# FIT_FPGA_POWER.net
KiCad netlist of a schematic drawn in Altium Designer
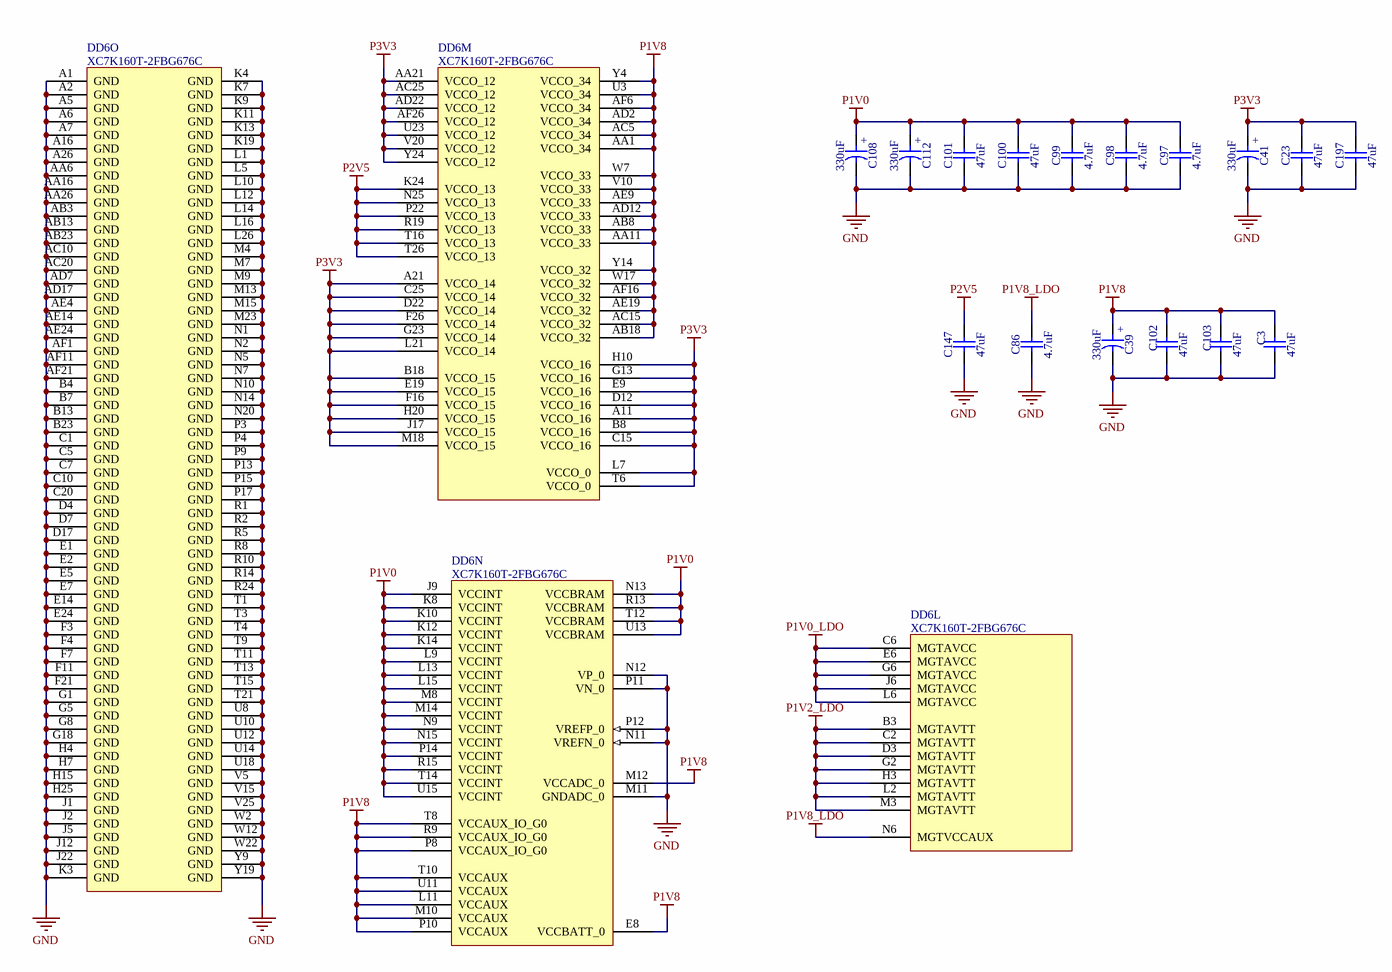
[diagram p0: FIT_FPGA_POWER.SchDoc]

(export (version "E")
  (design (tool "Eeschema 10.0.6"))
  (components
    (comp (ref "C3")
      (value "47uF")
      (footprint "CAPC3225X270N")
      (description "Non-polarised capacitor")
      (fields
        (field (name "PART NUMBER") "CC1210_47UF_16V_20%_X5R")
        (field (name "VOLTAGE") "16V")
        (field (name "AUTHOR") "CERN DEM MR")
      )
      (libsource (lib "Capacitors") (part "Capacitor - non polarized"))
    )
    (comp (ref "C23")
      (value "47uF")
      (footprint "CAPC3225X270N")
      (description "Non-polarised capacitor")
      (fields
        (field (name "PART NUMBER") "CC1210_47UF_16V_20%_X5R")
        (field (name "VOLTAGE") "16V")
        (field (name "AUTHOR") "CERN DEM MR")
      )
      (libsource (lib "Capacitors") (part "Capacitor - non polarized"))
    )
    (comp (ref "C39")
      (value "330uF")
      (footprint "CAPMP7343X300N")
      (description "Polarised capacitor")
      (fields
        (field (name "PART NUMBER") "CTE7343-30_330UF_4V_20%_PANASONIC_TPF")
        (field (name "VOLTAGE") "4V")
        (field (name "AUTHOR") "CERN DEM HF")
      )
      (libsource (lib "Capacitors") (part "Capacitor - polarized"))
    )
    (comp (ref "C41")
      (value "330uF")
      (footprint "CAPMP7343X310N")
      (description "Polarised capacitor")
      (fields
        (field (name "PART NUMBER") "CTE7343-31_330UF_6.3V_20%_LESR0015_KEMET_T520")
        (field (name "VOLTAGE") "6.3V")
        (field (name "AUTHOR") "CERN DEM JLC")
      )
      (libsource (lib "Capacitors") (part "Capacitor - polarized"))
    )
    (comp (ref "C86")
      (value "4.7uF")
      (footprint "CAPC2012X145N")
      (description "Non-polarised capacitor")
      (fields
        (field (name "PART NUMBER") "CC0805_4.7UF_50V_10%_X7R")
        (field (name "VOLTAGE") "50V")
        (field (name "AUTHOR") "CERN DEM JMW")
      )
      (libsource (lib "Capacitors") (part "Capacitor - non polarized"))
    )
    (comp (ref "C97")
      (value "4.7uF")
      (footprint "CAPC2012X145N")
      (description "Non-polarised capacitor")
      (fields
        (field (name "PART NUMBER") "CC0805_4.7UF_50V_10%_X7R")
        (field (name "VOLTAGE") "50V")
        (field (name "AUTHOR") "CERN DEM JMW")
      )
      (libsource (lib "Capacitors") (part "Capacitor - non polarized"))
    )
    (comp (ref "C98")
      (value "4.7uF")
      (footprint "CAPC2012X145N")
      (description "Non-polarised capacitor")
      (fields
        (field (name "PART NUMBER") "CC0805_4.7UF_50V_10%_X7R")
        (field (name "VOLTAGE") "50V")
        (field (name "AUTHOR") "CERN DEM JMW")
      )
      (libsource (lib "Capacitors") (part "Capacitor - non polarized"))
    )
    (comp (ref "C99")
      (value "4.7uF")
      (footprint "CAPC2012X145N")
      (description "Non-polarised capacitor")
      (fields
        (field (name "PART NUMBER") "CC0805_4.7UF_50V_10%_X7R")
        (field (name "VOLTAGE") "50V")
        (field (name "AUTHOR") "CERN DEM JMW")
      )
      (libsource (lib "Capacitors") (part "Capacitor - non polarized"))
    )
    (comp (ref "C100")
      (value "47uF")
      (footprint "CAPC3225X270N")
      (description "Non-polarised capacitor")
      (fields
        (field (name "PART NUMBER") "CC1210_47UF_16V_20%_X5R")
        (field (name "VOLTAGE") "16V")
        (field (name "AUTHOR") "CERN DEM MR")
      )
      (libsource (lib "Capacitors") (part "Capacitor - non polarized"))
    )
    (comp (ref "C101")
      (value "47uF")
      (footprint "CAPC3225X270N")
      (description "Non-polarised capacitor")
      (fields
        (field (name "PART NUMBER") "CC1210_47UF_16V_20%_X5R")
        (field (name "VOLTAGE") "16V")
        (field (name "AUTHOR") "CERN DEM MR")
      )
      (libsource (lib "Capacitors") (part "Capacitor - non polarized"))
    )
    (comp (ref "C102")
      (value "47uF")
      (footprint "CAPC3225X270N")
      (description "Non-polarised capacitor")
      (fields
        (field (name "PART NUMBER") "CC1210_47UF_16V_20%_X5R")
        (field (name "VOLTAGE") "16V")
        (field (name "AUTHOR") "CERN DEM MR")
      )
      (libsource (lib "Capacitors") (part "Capacitor - non polarized"))
    )
    (comp (ref "C103")
      (value "47uF")
      (footprint "CAPC3225X270N")
      (description "Non-polarised capacitor")
      (fields
        (field (name "PART NUMBER") "CC1210_47UF_16V_20%_X5R")
        (field (name "VOLTAGE") "16V")
        (field (name "AUTHOR") "CERN DEM MR")
      )
      (libsource (lib "Capacitors") (part "Capacitor - non polarized"))
    )
    (comp (ref "C108")
      (value "330uF")
      (footprint "CAPMP7343X190N")
      (description "Polarised capacitor")
      (fields
        (field (name "PART NUMBER") "CTE7343-19_330UF_2.5V_20%_LESR0009_KEMET_T520")
        (field (name "VOLTAGE") "2.5V")
        (field (name "AUTHOR") "CERN DEM HF")
      )
      (libsource (lib "Capacitors") (part "Capacitor - polarized"))
    )
    (comp (ref "C112")
      (value "330uF")
      (footprint "CAPMP7343X190N")
      (description "Polarised capacitor")
      (fields
        (field (name "PART NUMBER") "CTE7343-19_330UF_2.5V_20%_LESR0009_KEMET_T520")
        (field (name "VOLTAGE") "2.5V")
        (field (name "AUTHOR") "CERN DEM HF")
      )
      (libsource (lib "Capacitors") (part "Capacitor - polarized"))
    )
    (comp (ref "C147")
      (value "47uF")
      (footprint "CAPC3225X270N")
      (description "Non-polarised capacitor")
      (fields
        (field (name "PART NUMBER") "CC1210_47UF_16V_20%_X5R")
        (field (name "VOLTAGE") "16V")
        (field (name "AUTHOR") "CERN DEM MR")
      )
      (libsource (lib "Capacitors") (part "Capacitor - non polarized"))
    )
    (comp (ref "C197")
      (value "47uF")
      (footprint "CAPC3225X270N")
      (description "Non-polarised capacitor")
      (fields
        (field (name "PART NUMBER") "CC1210_47UF_16V_20%_X5R")
        (field (name "VOLTAGE") "16V")
        (field (name "AUTHOR") "CERN DEM MR")
      )
      (libsource (lib "Capacitors") (part "Capacitor - non polarized"))
    )
    (comp (ref "DD6")
      (value "XC7K160T-2FBG676C")
      (footprint "BGA676C100P26X26_2700X2700X254")
      (description "KINTEX-7, FPGA, 676-Ball BGA, Pb-Free")
      (fields (field (name "MANUFACTURER") "XILINX") (field (name "AUTHOR") "CERN DEM BC"))
      (libsource (lib "ICs And Semiconductors") (part "XC7K160T-xFBG676"))
    )
  )
  (nets
    (net (code "1") (name "GND") (class "Default")
      (node (ref "C100") (pin "1") (pinfunction "1_1") (pintype "passive"))
      (node (ref "C101") (pin "1") (pinfunction "1_1") (pintype "passive"))
      (node (ref "C102") (pin "1") (pinfunction "1_1") (pintype "passive"))
      (node (ref "C103") (pin "1") (pinfunction "1_1") (pintype "passive"))
      (node (ref "C108") (pin "2") (pinfunction "2_2") (pintype "passive"))
      (node (ref "C112") (pin "2") (pinfunction "2_2") (pintype "passive"))
      (node (ref "C147") (pin "1") (pinfunction "1_1") (pintype "passive"))
      (node (ref "C197") (pin "1") (pinfunction "1_1") (pintype "passive"))
      (node (ref "C23") (pin "1") (pinfunction "1_1") (pintype "passive"))
      (node (ref "C3") (pin "1") (pinfunction "1_1") (pintype "passive"))
      (node (ref "C39") (pin "2") (pinfunction "2_2") (pintype "passive"))
      (node (ref "C41") (pin "2") (pinfunction "2_2") (pintype "passive"))
      (node (ref "C86") (pin "1") (pinfunction "1_1") (pintype "passive"))
      (node (ref "C97") (pin "1") (pinfunction "1_1") (pintype "passive"))
      (node (ref "C98") (pin "1") (pinfunction "1_1") (pintype "passive"))
      (node (ref "C99") (pin "1") (pinfunction "1_1") (pintype "passive"))
      (node (ref "DD6") (pin "A1") (pinfunction "GND_A1") (pintype "power_in"))
      (node (ref "DD6") (pin "A16") (pinfunction "GND_A16") (pintype "power_in"))
      (node (ref "DD6") (pin "A2") (pinfunction "GND_A2") (pintype "power_in"))
      (node (ref "DD6") (pin "A26") (pinfunction "GND_A26") (pintype "power_in"))
      (node (ref "DD6") (pin "A5") (pinfunction "GND_A5") (pintype "power_in"))
      (node (ref "DD6") (pin "A6") (pinfunction "GND_A6") (pintype "power_in"))
      (node (ref "DD6") (pin "A7") (pinfunction "GND_A7") (pintype "power_in"))
      (node (ref "DD6") (pin "AA16") (pinfunction "GND_AA16") (pintype "power_in"))
      (node (ref "DD6") (pin "AA26") (pinfunction "GND_AA26") (pintype "power_in"))
      (node (ref "DD6") (pin "AA6") (pinfunction "GND_AA6") (pintype "power_in"))
      (node (ref "DD6") (pin "AB13") (pinfunction "GND_AB13") (pintype "power_in"))
      (node (ref "DD6") (pin "AB23") (pinfunction "GND_AB23") (pintype "power_in"))
      (node (ref "DD6") (pin "AB3") (pinfunction "GND_AB3") (pintype "power_in"))
      (node (ref "DD6") (pin "AC10") (pinfunction "GND_AC10") (pintype "power_in"))
      (node (ref "DD6") (pin "AC20") (pinfunction "GND_AC20") (pintype "power_in"))
      (node (ref "DD6") (pin "AD17") (pinfunction "GND_AD17") (pintype "power_in"))
      (node (ref "DD6") (pin "AD7") (pinfunction "GND_AD7") (pintype "power_in"))
      (node (ref "DD6") (pin "AE14") (pinfunction "GND_AE14") (pintype "power_in"))
      (node (ref "DD6") (pin "AE24") (pinfunction "GND_AE24") (pintype "power_in"))
      (node (ref "DD6") (pin "AE4") (pinfunction "GND_AE4") (pintype "power_in"))
      (node (ref "DD6") (pin "AF1") (pinfunction "GND_AF1") (pintype "power_in"))
      (node (ref "DD6") (pin "AF11") (pinfunction "GND_AF11") (pintype "power_in"))
      (node (ref "DD6") (pin "AF21") (pinfunction "GND_AF21") (pintype "power_in"))
      (node (ref "DD6") (pin "B13") (pinfunction "GND_B13") (pintype "power_in"))
      (node (ref "DD6") (pin "B23") (pinfunction "GND_B23") (pintype "power_in"))
      (node (ref "DD6") (pin "B4") (pinfunction "GND_B4") (pintype "power_in"))
      (node (ref "DD6") (pin "B7") (pinfunction "GND_B7") (pintype "power_in"))
      (node (ref "DD6") (pin "C1") (pinfunction "GND_C1") (pintype "power_in"))
      (node (ref "DD6") (pin "C10") (pinfunction "GND_C10") (pintype "power_in"))
      (node (ref "DD6") (pin "C20") (pinfunction "GND_C20") (pintype "power_in"))
      (node (ref "DD6") (pin "C5") (pinfunction "GND_C5") (pintype "power_in"))
      (node (ref "DD6") (pin "C7") (pinfunction "GND_C7") (pintype "power_in"))
      (node (ref "DD6") (pin "D17") (pinfunction "GND_D17") (pintype "power_in"))
      (node (ref "DD6") (pin "D4") (pinfunction "GND_D4") (pintype "power_in"))
      (node (ref "DD6") (pin "D7") (pinfunction "GND_D7") (pintype "power_in"))
      (node (ref "DD6") (pin "E1") (pinfunction "GND_E1") (pintype "power_in"))
      (node (ref "DD6") (pin "E14") (pinfunction "GND_E14") (pintype "power_in"))
      (node (ref "DD6") (pin "E2") (pinfunction "GND_E2") (pintype "power_in"))
      (node (ref "DD6") (pin "E24") (pinfunction "GND_E24") (pintype "power_in"))
      (node (ref "DD6") (pin "E5") (pinfunction "GND_E5") (pintype "power_in"))
      (node (ref "DD6") (pin "E7") (pinfunction "GND_E7") (pintype "power_in"))
      (node (ref "DD6") (pin "F11") (pinfunction "GND_F11") (pintype "power_in"))
      (node (ref "DD6") (pin "F21") (pinfunction "GND_F21") (pintype "power_in"))
      (node (ref "DD6") (pin "F3") (pinfunction "GND_F3") (pintype "power_in"))
      (node (ref "DD6") (pin "F4") (pinfunction "GND_F4") (pintype "power_in"))
      (node (ref "DD6") (pin "F7") (pinfunction "GND_F7") (pintype "power_in"))
      (node (ref "DD6") (pin "G1") (pinfunction "GND_G1") (pintype "power_in"))
      (node (ref "DD6") (pin "G18") (pinfunction "GND_G18") (pintype "power_in"))
      (node (ref "DD6") (pin "G5") (pinfunction "GND_G5") (pintype "power_in"))
      (node (ref "DD6") (pin "G8") (pinfunction "GND_G8") (pintype "power_in"))
      (node (ref "DD6") (pin "H15") (pinfunction "GND_H15") (pintype "power_in"))
      (node (ref "DD6") (pin "H25") (pinfunction "GND_H25") (pintype "power_in"))
      (node (ref "DD6") (pin "H4") (pinfunction "GND_H4") (pintype "power_in"))
      (node (ref "DD6") (pin "H7") (pinfunction "GND_H7") (pintype "power_in"))
      (node (ref "DD6") (pin "J1") (pinfunction "GND_J1") (pintype "power_in"))
      (node (ref "DD6") (pin "J12") (pinfunction "GND_J12") (pintype "power_in"))
      (node (ref "DD6") (pin "J2") (pinfunction "GND_J2") (pintype "power_in"))
      (node (ref "DD6") (pin "J22") (pinfunction "GND_J22") (pintype "power_in"))
      (node (ref "DD6") (pin "J5") (pinfunction "GND_J5") (pintype "power_in"))
      (node (ref "DD6") (pin "K11") (pinfunction "GND_K11") (pintype "power_in"))
      (node (ref "DD6") (pin "K13") (pinfunction "GND_K13") (pintype "power_in"))
      (node (ref "DD6") (pin "K19") (pinfunction "GND_K19") (pintype "power_in"))
      (node (ref "DD6") (pin "K3") (pinfunction "GND_K3") (pintype "power_in"))
      (node (ref "DD6") (pin "K4") (pinfunction "GND_K4") (pintype "power_in"))
      (node (ref "DD6") (pin "K7") (pinfunction "GND_K7") (pintype "power_in"))
      (node (ref "DD6") (pin "K9") (pinfunction "GND_K9") (pintype "power_in"))
      (node (ref "DD6") (pin "L1") (pinfunction "GND_L1") (pintype "power_in"))
      (node (ref "DD6") (pin "L10") (pinfunction "GND_L10") (pintype "power_in"))
      (node (ref "DD6") (pin "L12") (pinfunction "GND_L12") (pintype "power_in"))
      (node (ref "DD6") (pin "L14") (pinfunction "GND_L14") (pintype "power_in"))
      (node (ref "DD6") (pin "L16") (pinfunction "GND_L16") (pintype "power_in"))
      (node (ref "DD6") (pin "L26") (pinfunction "GND_L26") (pintype "power_in"))
      (node (ref "DD6") (pin "L5") (pinfunction "GND_L5") (pintype "power_in"))
      (node (ref "DD6") (pin "M11") (pinfunction "GNDADC_0_M11") (pintype "power_in"))
      (node (ref "DD6") (pin "M13") (pinfunction "GND_M13") (pintype "power_in"))
      (node (ref "DD6") (pin "M15") (pinfunction "GND_M15") (pintype "power_in"))
      (node (ref "DD6") (pin "M23") (pinfunction "GND_M23") (pintype "power_in"))
      (node (ref "DD6") (pin "M4") (pinfunction "GND_M4") (pintype "power_in"))
      (node (ref "DD6") (pin "M7") (pinfunction "GND_M7") (pintype "power_in"))
      (node (ref "DD6") (pin "M9") (pinfunction "GND_M9") (pintype "power_in"))
      (node (ref "DD6") (pin "N1") (pinfunction "GND_N1") (pintype "power_in"))
      (node (ref "DD6") (pin "N10") (pinfunction "GND_N10") (pintype "power_in"))
      (node (ref "DD6") (pin "N11") (pinfunction "VREFN_0_N11") (pintype "input"))
      (node (ref "DD6") (pin "N12") (pinfunction "VP_0_N12") (pintype "power_in"))
      (node (ref "DD6") (pin "N14") (pinfunction "GND_N14") (pintype "power_in"))
      (node (ref "DD6") (pin "N2") (pinfunction "GND_N2") (pintype "power_in"))
      (node (ref "DD6") (pin "N20") (pinfunction "GND_N20") (pintype "power_in"))
      (node (ref "DD6") (pin "N5") (pinfunction "GND_N5") (pintype "power_in"))
      (node (ref "DD6") (pin "N7") (pinfunction "GND_N7") (pintype "power_in"))
      (node (ref "DD6") (pin "P11") (pinfunction "VN_0_P11") (pintype "power_in"))
      (node (ref "DD6") (pin "P12") (pinfunction "VREFP_0_P12") (pintype "input"))
      (node (ref "DD6") (pin "P13") (pinfunction "GND_P13") (pintype "power_in"))
      (node (ref "DD6") (pin "P15") (pinfunction "GND_P15") (pintype "power_in"))
      (node (ref "DD6") (pin "P17") (pinfunction "GND_P17") (pintype "power_in"))
      (node (ref "DD6") (pin "P3") (pinfunction "GND_P3") (pintype "power_in"))
      (node (ref "DD6") (pin "P4") (pinfunction "GND_P4") (pintype "power_in"))
      (node (ref "DD6") (pin "P9") (pinfunction "GND_P9") (pintype "power_in"))
      (node (ref "DD6") (pin "R1") (pinfunction "GND_R1") (pintype "power_in"))
      (node (ref "DD6") (pin "R10") (pinfunction "GND_R10") (pintype "power_in"))
      (node (ref "DD6") (pin "R14") (pinfunction "GND_R14") (pintype "power_in"))
      (node (ref "DD6") (pin "R2") (pinfunction "GND_R2") (pintype "power_in"))
      (node (ref "DD6") (pin "R24") (pinfunction "GND_R24") (pintype "power_in"))
      (node (ref "DD6") (pin "R5") (pinfunction "GND_R5") (pintype "power_in"))
      (node (ref "DD6") (pin "R8") (pinfunction "GND_R8") (pintype "power_in"))
      (node (ref "DD6") (pin "T1") (pinfunction "GND_T1") (pintype "power_in"))
      (node (ref "DD6") (pin "T11") (pinfunction "GND_T11") (pintype "power_in"))
      (node (ref "DD6") (pin "T13") (pinfunction "GND_T13") (pintype "power_in"))
      (node (ref "DD6") (pin "T15") (pinfunction "GND_T15") (pintype "power_in"))
      (node (ref "DD6") (pin "T21") (pinfunction "GND_T21") (pintype "power_in"))
      (node (ref "DD6") (pin "T3") (pinfunction "GND_T3") (pintype "power_in"))
      (node (ref "DD6") (pin "T4") (pinfunction "GND_T4") (pintype "power_in"))
      (node (ref "DD6") (pin "T9") (pinfunction "GND_T9") (pintype "power_in"))
      (node (ref "DD6") (pin "U10") (pinfunction "GND_U10") (pintype "power_in"))
      (node (ref "DD6") (pin "U12") (pinfunction "GND_U12") (pintype "power_in"))
      (node (ref "DD6") (pin "U14") (pinfunction "GND_U14") (pintype "power_in"))
      (node (ref "DD6") (pin "U18") (pinfunction "GND_U18") (pintype "power_in"))
      (node (ref "DD6") (pin "U8") (pinfunction "GND_U8") (pintype "power_in"))
      (node (ref "DD6") (pin "V15") (pinfunction "GND_V15") (pintype "power_in"))
      (node (ref "DD6") (pin "V25") (pinfunction "GND_V25") (pintype "power_in"))
      (node (ref "DD6") (pin "V5") (pinfunction "GND_V5") (pintype "power_in"))
      (node (ref "DD6") (pin "W12") (pinfunction "GND_W12") (pintype "power_in"))
      (node (ref "DD6") (pin "W2") (pinfunction "GND_W2") (pintype "power_in"))
      (node (ref "DD6") (pin "W22") (pinfunction "GND_W22") (pintype "power_in"))
      (node (ref "DD6") (pin "Y19") (pinfunction "GND_Y19") (pintype "power_in"))
      (node (ref "DD6") (pin "Y9") (pinfunction "GND_Y9") (pintype "power_in"))
    )
    (net (code "2") (name "P1V0") (class "Default")
      (node (ref "C100") (pin "2") (pinfunction "2_2") (pintype "passive"))
      (node (ref "C101") (pin "2") (pinfunction "2_2") (pintype "passive"))
      (node (ref "C108") (pin "1") (pinfunction "1_1") (pintype "passive"))
      (node (ref "C112") (pin "1") (pinfunction "1_1") (pintype "passive"))
      (node (ref "C97") (pin "2") (pinfunction "2_2") (pintype "passive"))
      (node (ref "C98") (pin "2") (pinfunction "2_2") (pintype "passive"))
      (node (ref "C99") (pin "2") (pinfunction "2_2") (pintype "passive"))
      (node (ref "DD6") (pin "J9") (pinfunction "VCCINT_J9") (pintype "power_in"))
      (node (ref "DD6") (pin "K10") (pinfunction "VCCINT_K10") (pintype "power_in"))
      (node (ref "DD6") (pin "K12") (pinfunction "VCCINT_K12") (pintype "power_in"))
      (node (ref "DD6") (pin "K14") (pinfunction "VCCINT_K14") (pintype "power_in"))
      (node (ref "DD6") (pin "K8") (pinfunction "VCCINT_K8") (pintype "power_in"))
      (node (ref "DD6") (pin "L13") (pinfunction "VCCINT_L13") (pintype "power_in"))
      (node (ref "DD6") (pin "L15") (pinfunction "VCCINT_L15") (pintype "power_in"))
      (node (ref "DD6") (pin "L9") (pinfunction "VCCINT_L9") (pintype "power_in"))
      (node (ref "DD6") (pin "M14") (pinfunction "VCCINT_M14") (pintype "power_in"))
      (node (ref "DD6") (pin "M8") (pinfunction "VCCINT_M8") (pintype "power_in"))
      (node (ref "DD6") (pin "N13") (pinfunction "VCCBRAM_N13") (pintype "power_in"))
      (node (ref "DD6") (pin "N15") (pinfunction "VCCINT_N15") (pintype "power_in"))
      (node (ref "DD6") (pin "N9") (pinfunction "VCCINT_N9") (pintype "power_in"))
      (node (ref "DD6") (pin "P14") (pinfunction "VCCINT_P14") (pintype "power_in"))
      (node (ref "DD6") (pin "R13") (pinfunction "VCCBRAM_R13") (pintype "power_in"))
      (node (ref "DD6") (pin "R15") (pinfunction "VCCINT_R15") (pintype "power_in"))
      (node (ref "DD6") (pin "T12") (pinfunction "VCCBRAM_T12") (pintype "power_in"))
      (node (ref "DD6") (pin "T14") (pinfunction "VCCINT_T14") (pintype "power_in"))
      (node (ref "DD6") (pin "U13") (pinfunction "VCCBRAM_U13") (pintype "power_in"))
      (node (ref "DD6") (pin "U15") (pinfunction "VCCINT_U15") (pintype "power_in"))
    )
    (net (code "3") (name "P1V0_LDO") (class "Default")
      (node (ref "DD6") (pin "C6") (pinfunction "MGTAVCC_C6") (pintype "power_in"))
      (node (ref "DD6") (pin "E6") (pinfunction "MGTAVCC_E6") (pintype "power_in"))
      (node (ref "DD6") (pin "G6") (pinfunction "MGTAVCC_G6") (pintype "power_in"))
      (node (ref "DD6") (pin "J6") (pinfunction "MGTAVCC_J6") (pintype "power_in"))
      (node (ref "DD6") (pin "L6") (pinfunction "MGTAVCC_L6") (pintype "power_in"))
    )
    (net (code "4") (name "P1V2_LDO") (class "Default")
      (node (ref "DD6") (pin "B3") (pinfunction "MGTAVTT_B3") (pintype "power_in"))
      (node (ref "DD6") (pin "C2") (pinfunction "MGTAVTT_C2") (pintype "power_in"))
      (node (ref "DD6") (pin "D3") (pinfunction "MGTAVTT_D3") (pintype "power_in"))
      (node (ref "DD6") (pin "G2") (pinfunction "MGTAVTT_G2") (pintype "power_in"))
      (node (ref "DD6") (pin "H3") (pinfunction "MGTAVTT_H3") (pintype "power_in"))
      (node (ref "DD6") (pin "L2") (pinfunction "MGTAVTT_L2") (pintype "power_in"))
      (node (ref "DD6") (pin "M3") (pinfunction "MGTAVTT_M3") (pintype "power_in"))
    )
    (net (code "5") (name "P1V8") (class "Default")
      (node (ref "C102") (pin "2") (pinfunction "2_2") (pintype "passive"))
      (node (ref "C103") (pin "2") (pinfunction "2_2") (pintype "passive"))
      (node (ref "C3") (pin "2") (pinfunction "2_2") (pintype "passive"))
      (node (ref "C39") (pin "1") (pinfunction "1_1") (pintype "passive"))
      (node (ref "DD6") (pin "AA1") (pinfunction "VCCO_34_AA1") (pintype "power_in"))
      (node (ref "DD6") (pin "AA11") (pinfunction "VCCO_33_AA11") (pintype "power_in"))
      (node (ref "DD6") (pin "AB18") (pinfunction "VCCO_32_AB18") (pintype "power_in"))
      (node (ref "DD6") (pin "AB8") (pinfunction "VCCO_33_AB8") (pintype "power_in"))
      (node (ref "DD6") (pin "AC15") (pinfunction "VCCO_32_AC15") (pintype "power_in"))
      (node (ref "DD6") (pin "AC5") (pinfunction "VCCO_34_AC5") (pintype "power_in"))
      (node (ref "DD6") (pin "AD12") (pinfunction "VCCO_33_AD12") (pintype "power_in"))
      (node (ref "DD6") (pin "AD2") (pinfunction "VCCO_34_AD2") (pintype "power_in"))
      (node (ref "DD6") (pin "AE19") (pinfunction "VCCO_32_AE19") (pintype "power_in"))
      (node (ref "DD6") (pin "AE9") (pinfunction "VCCO_33_AE9") (pintype "power_in"))
      (node (ref "DD6") (pin "AF16") (pinfunction "VCCO_32_AF16") (pintype "power_in"))
      (node (ref "DD6") (pin "AF6") (pinfunction "VCCO_34_AF6") (pintype "power_in"))
      (node (ref "DD6") (pin "E8") (pinfunction "VCCBATT_0_E8") (pintype "power_in"))
      (node (ref "DD6") (pin "L11") (pinfunction "VCCAUX_L11") (pintype "power_in"))
      (node (ref "DD6") (pin "M10") (pinfunction "VCCAUX_M10") (pintype "power_in"))
      (node (ref "DD6") (pin "M12") (pinfunction "VCCADC_0_M12") (pintype "power_in"))
      (node (ref "DD6") (pin "P10") (pinfunction "VCCAUX_P10") (pintype "power_in"))
      (node (ref "DD6") (pin "P8") (pinfunction "VCCAUX_IO_G0_P8") (pintype "power_in"))
      (node (ref "DD6") (pin "R9") (pinfunction "VCCAUX_IO_G0_R9") (pintype "power_in"))
      (node (ref "DD6") (pin "T10") (pinfunction "VCCAUX_T10") (pintype "power_in"))
      (node (ref "DD6") (pin "T8") (pinfunction "VCCAUX_IO_G0_T8") (pintype "power_in"))
      (node (ref "DD6") (pin "U11") (pinfunction "VCCAUX_U11") (pintype "power_in"))
      (node (ref "DD6") (pin "U3") (pinfunction "VCCO_34_U3") (pintype "power_in"))
      (node (ref "DD6") (pin "V10") (pinfunction "VCCO_33_V10") (pintype "power_in"))
      (node (ref "DD6") (pin "W17") (pinfunction "VCCO_32_W17") (pintype "power_in"))
      (node (ref "DD6") (pin "W7") (pinfunction "VCCO_33_W7") (pintype "power_in"))
      (node (ref "DD6") (pin "Y14") (pinfunction "VCCO_32_Y14") (pintype "power_in"))
      (node (ref "DD6") (pin "Y4") (pinfunction "VCCO_34_Y4") (pintype "power_in"))
    )
    (net (code "6") (name "P1V8_LDO") (class "Default")
      (node (ref "C86") (pin "2") (pinfunction "2_2") (pintype "passive"))
      (node (ref "DD6") (pin "N6") (pinfunction "MGTVCCAUX_N6") (pintype "power_in"))
    )
    (net (code "7") (name "P2V5") (class "Default")
      (node (ref "C147") (pin "2") (pinfunction "2_2") (pintype "passive"))
      (node (ref "DD6") (pin "K24") (pinfunction "VCCO_13_K24") (pintype "power_in"))
      (node (ref "DD6") (pin "N25") (pinfunction "VCCO_13_N25") (pintype "power_in"))
      (node (ref "DD6") (pin "P22") (pinfunction "VCCO_13_P22") (pintype "power_in"))
      (node (ref "DD6") (pin "R19") (pinfunction "VCCO_13_R19") (pintype "power_in"))
      (node (ref "DD6") (pin "T16") (pinfunction "VCCO_13_T16") (pintype "power_in"))
      (node (ref "DD6") (pin "T26") (pinfunction "VCCO_13_T26") (pintype "power_in"))
    )
    (net (code "8") (name "P3V3") (class "Default")
      (node (ref "C197") (pin "2") (pinfunction "2_2") (pintype "passive"))
      (node (ref "C23") (pin "2") (pinfunction "2_2") (pintype "passive"))
      (node (ref "C41") (pin "1") (pinfunction "1_1") (pintype "passive"))
      (node (ref "DD6") (pin "A11") (pinfunction "VCCO_16_A11") (pintype "power_in"))
      (node (ref "DD6") (pin "A21") (pinfunction "VCCO_14_A21") (pintype "power_in"))
      (node (ref "DD6") (pin "AA21") (pinfunction "VCCO_12_AA21") (pintype "power_in"))
      (node (ref "DD6") (pin "AC25") (pinfunction "VCCO_12_AC25") (pintype "power_in"))
      (node (ref "DD6") (pin "AD22") (pinfunction "VCCO_12_AD22") (pintype "power_in"))
      (node (ref "DD6") (pin "AF26") (pinfunction "VCCO_12_AF26") (pintype "power_in"))
      (node (ref "DD6") (pin "B18") (pinfunction "VCCO_15_B18") (pintype "power_in"))
      (node (ref "DD6") (pin "B8") (pinfunction "VCCO_16_B8") (pintype "power_in"))
      (node (ref "DD6") (pin "C15") (pinfunction "VCCO_16_C15") (pintype "power_in"))
      (node (ref "DD6") (pin "C25") (pinfunction "VCCO_14_C25") (pintype "power_in"))
      (node (ref "DD6") (pin "D12") (pinfunction "VCCO_16_D12") (pintype "power_in"))
      (node (ref "DD6") (pin "D22") (pinfunction "VCCO_14_D22") (pintype "power_in"))
      (node (ref "DD6") (pin "E19") (pinfunction "VCCO_15_E19") (pintype "power_in"))
      (node (ref "DD6") (pin "E9") (pinfunction "VCCO_16_E9") (pintype "power_in"))
      (node (ref "DD6") (pin "F16") (pinfunction "VCCO_15_F16") (pintype "power_in"))
      (node (ref "DD6") (pin "F26") (pinfunction "VCCO_14_F26") (pintype "power_in"))
      (node (ref "DD6") (pin "G13") (pinfunction "VCCO_16_G13") (pintype "power_in"))
      (node (ref "DD6") (pin "G23") (pinfunction "VCCO_14_G23") (pintype "power_in"))
      (node (ref "DD6") (pin "H10") (pinfunction "VCCO_16_H10") (pintype "power_in"))
      (node (ref "DD6") (pin "H20") (pinfunction "VCCO_15_H20") (pintype "power_in"))
      (node (ref "DD6") (pin "J17") (pinfunction "VCCO_15_J17") (pintype "power_in"))
      (node (ref "DD6") (pin "L21") (pinfunction "VCCO_14_L21") (pintype "power_in"))
      (node (ref "DD6") (pin "L7") (pinfunction "VCCO_0_L7") (pintype "power_in"))
      (node (ref "DD6") (pin "M18") (pinfunction "VCCO_15_M18") (pintype "power_in"))
      (node (ref "DD6") (pin "T6") (pinfunction "VCCO_0_T6") (pintype "power_in"))
      (node (ref "DD6") (pin "U23") (pinfunction "VCCO_12_U23") (pintype "power_in"))
      (node (ref "DD6") (pin "V20") (pinfunction "VCCO_12_V20") (pintype "power_in"))
      (node (ref "DD6") (pin "Y24") (pinfunction "VCCO_12_Y24") (pintype "power_in"))
    )
  )
)
